# InkTime_Schematic.net
KiCad netlist of a schematic drawn in EAGLE
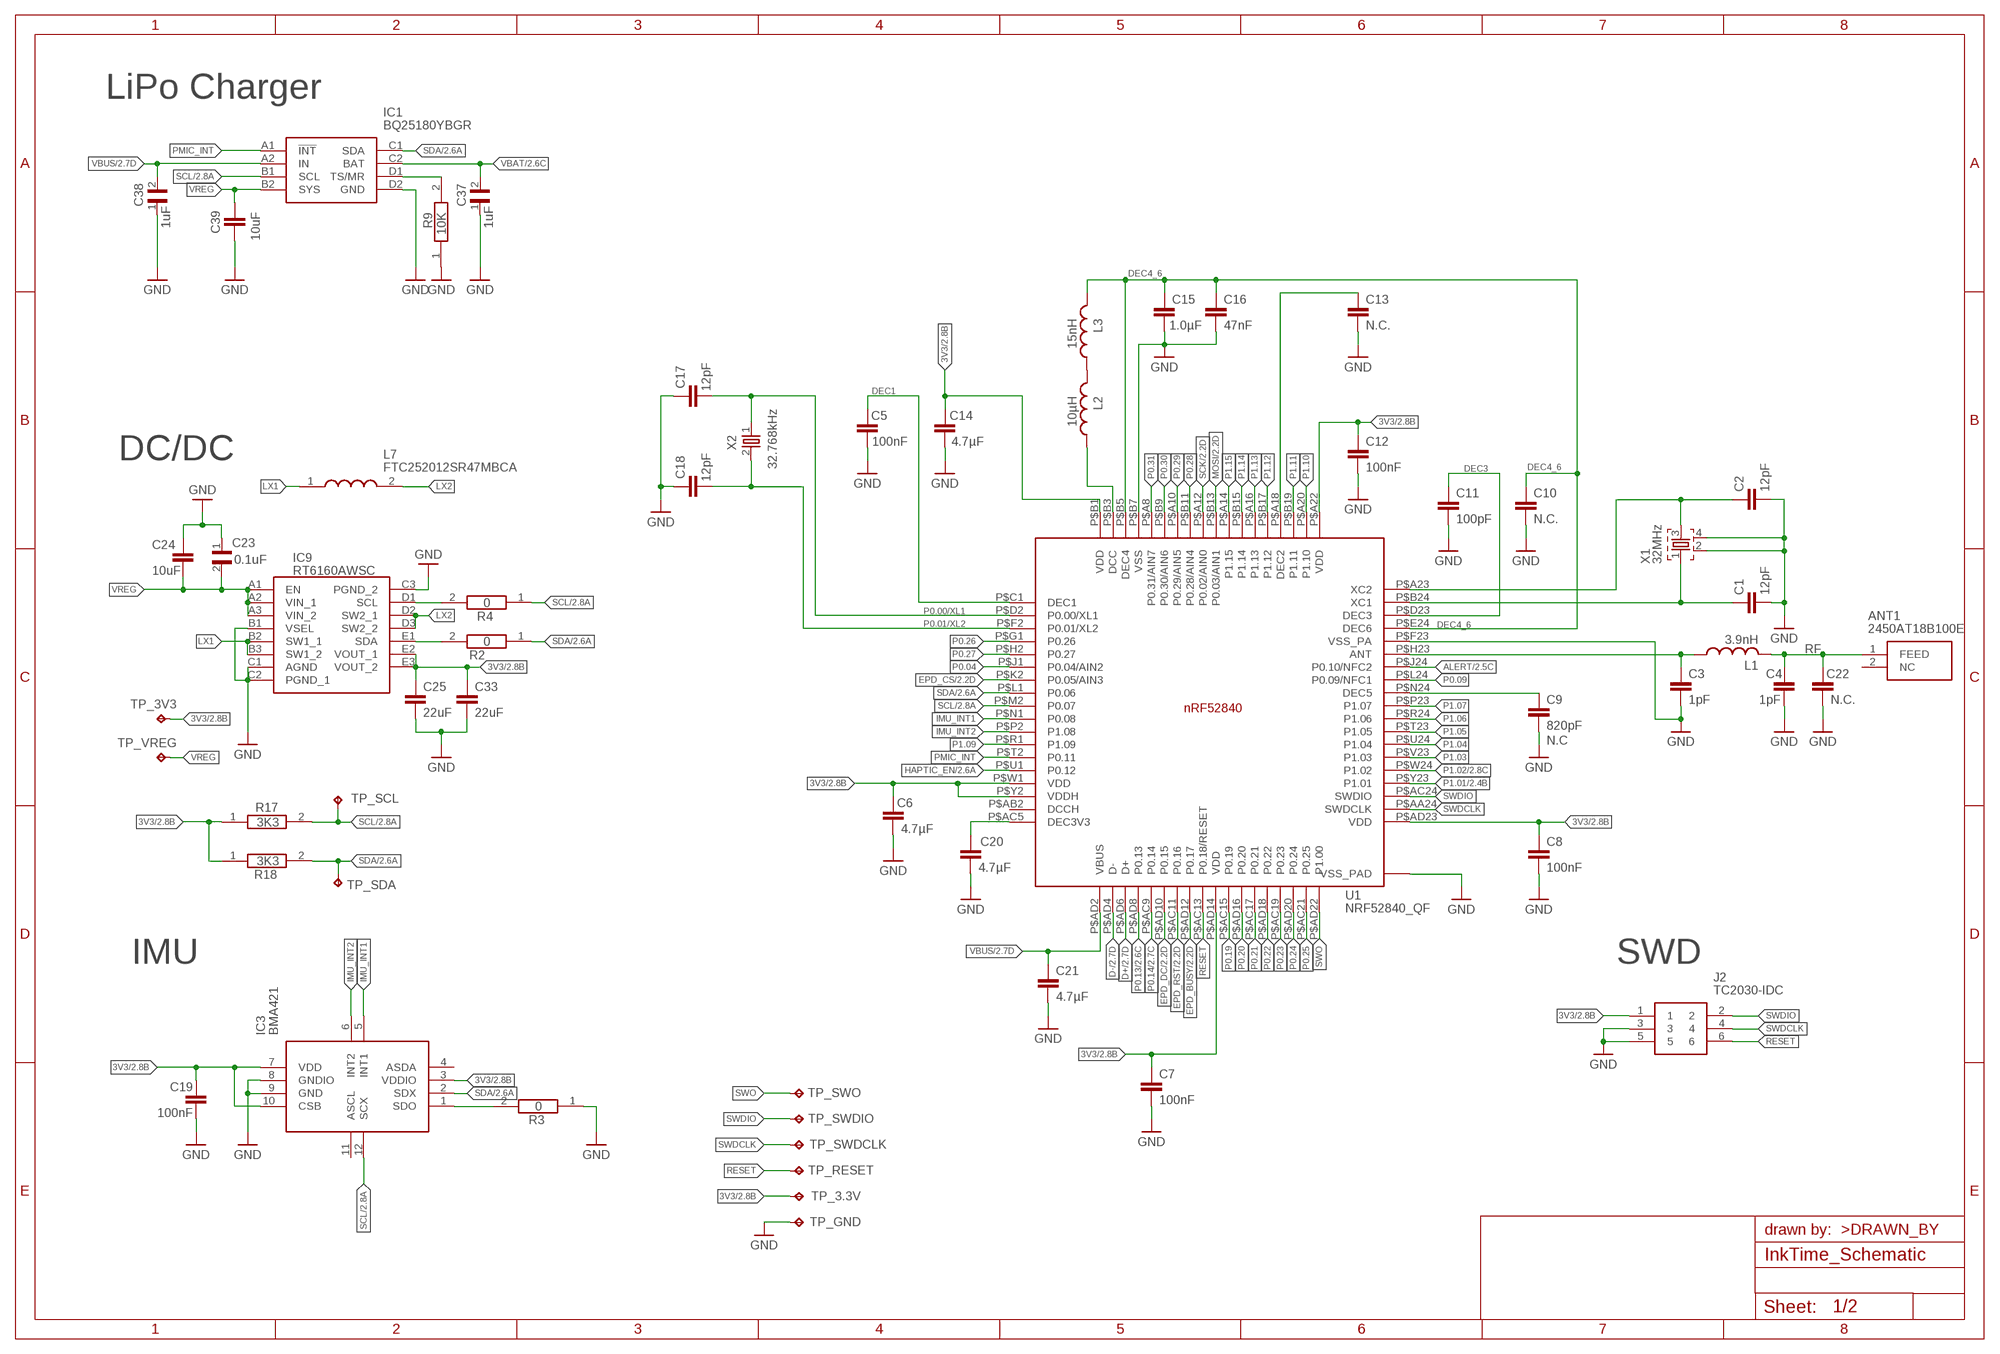
[diagram p0: schematic, sheet 1]
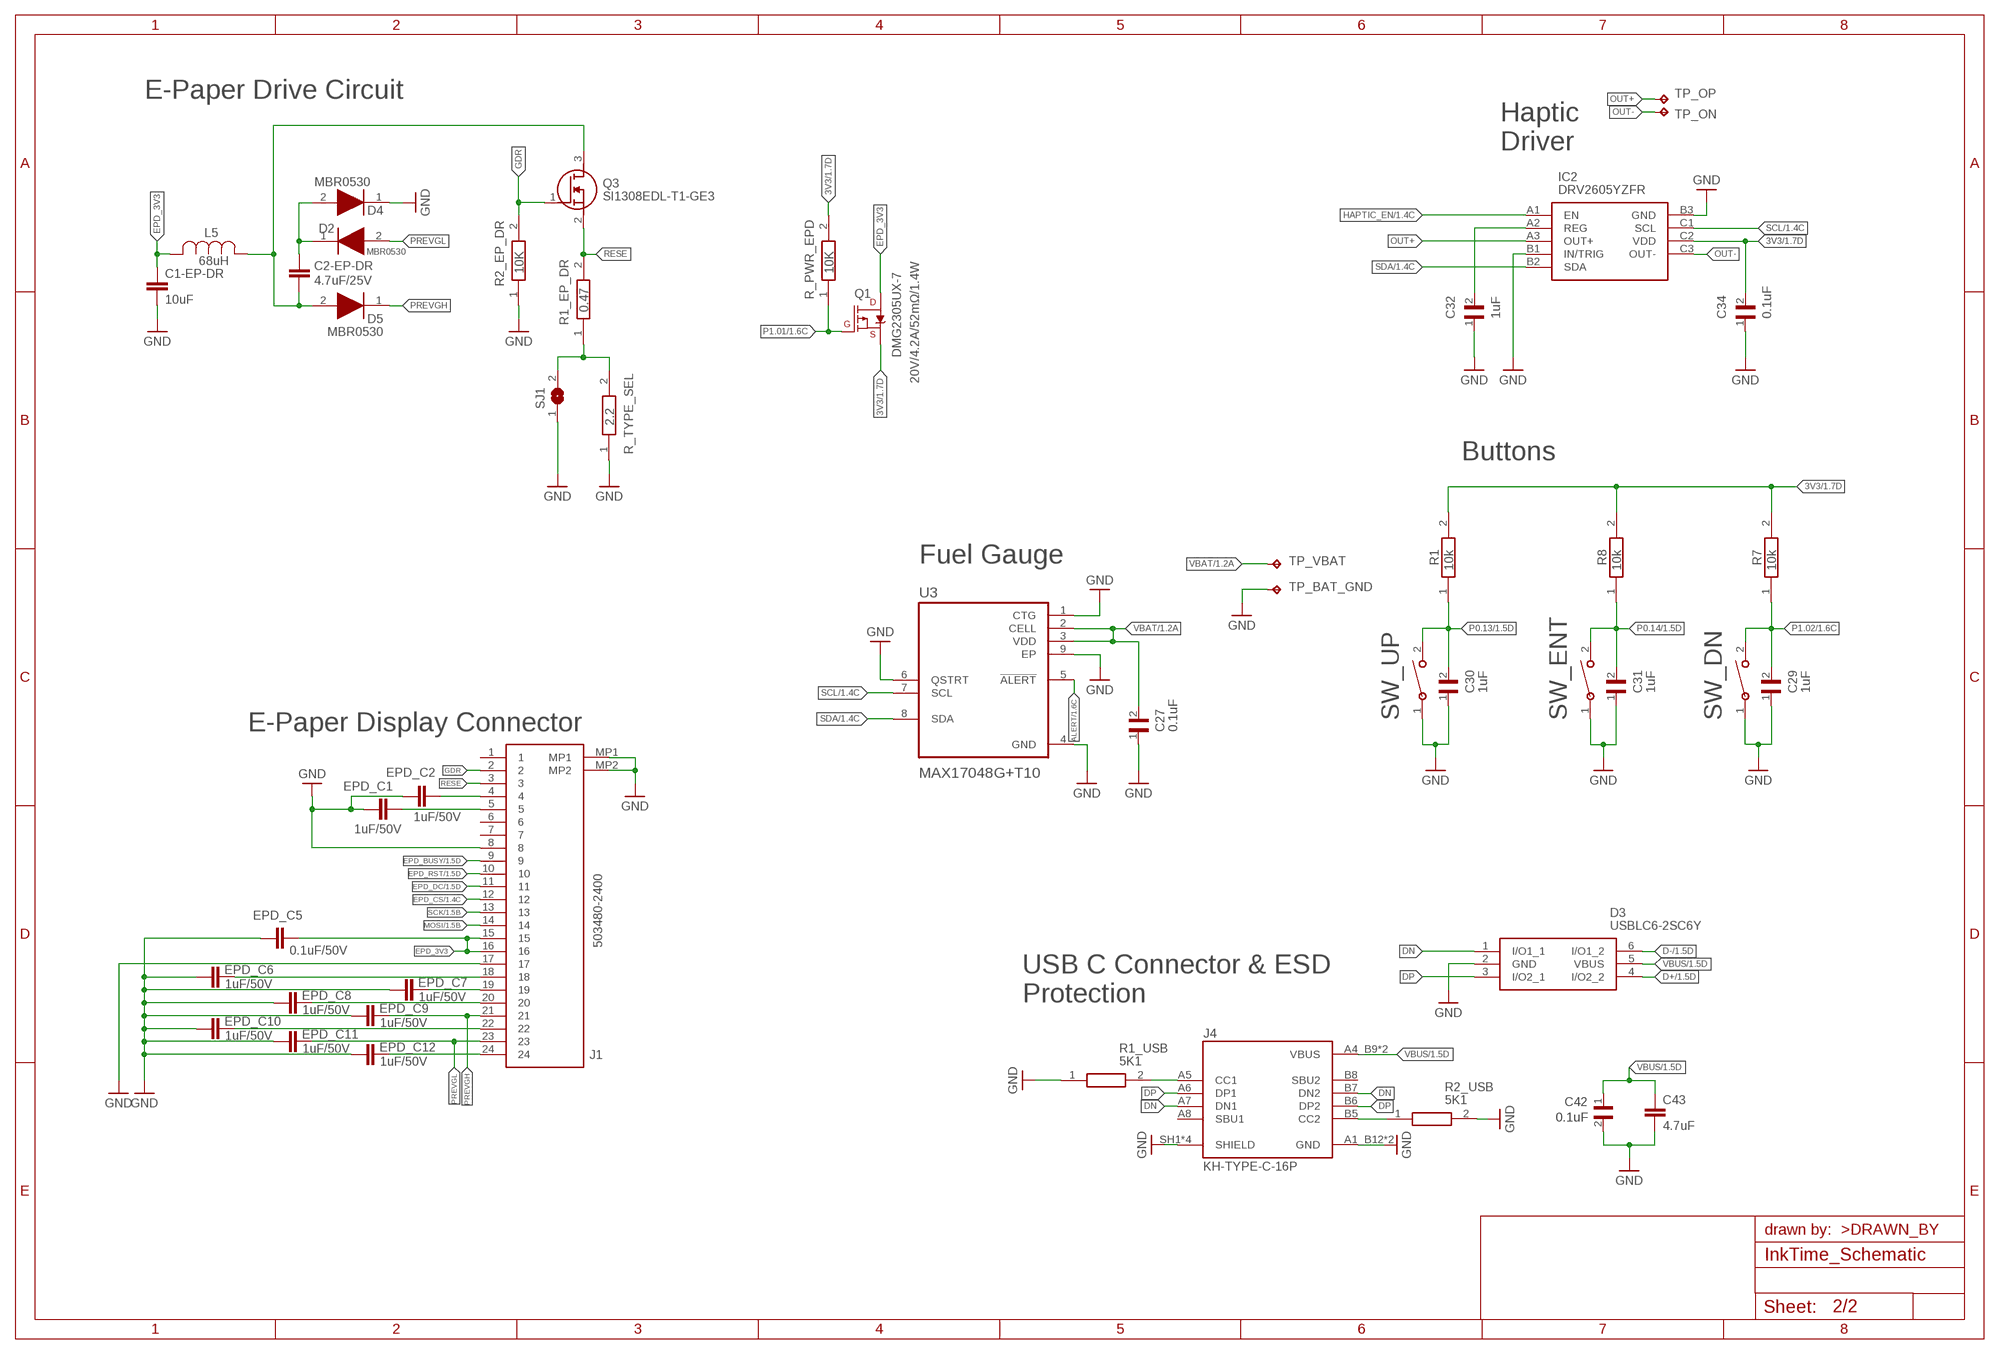
[diagram p1: schematic, sheet 2]

(export (version "E")
  (design (tool "Eeschema 10.0.6"))
  (components
    (comp (ref "C1-EP-DR")
      (value "10uF")
      (footprint "eagle-import:NORDIC_NRF_3_RESC0402_L")
      (libsource (lib "eagle-import") (part "NORDIC_NRF_3_CAPACITOR_0402_L"))
    )
    (comp (ref "C2-EP-DR")
      (value "4.7uF/25V")
      (footprint "eagle-import:NORDIC_NRF_3_RESC0402_L")
      (libsource (lib "eagle-import") (part "NORDIC_NRF_3_CAPACITOR_0402_L"))
    )
    (comp (ref "C27")
      (value "0.1uF")
      (footprint "eagle-import:GRM011R60J152KE01L_1_0201")
      (libsource (lib "eagle-import") (part "GRM011R60J152KE01L_1_GRM011R60J152KE01L"))
    )
    (comp (ref "C29")
      (value "1uF")
      (footprint "eagle-import:GRM011R60J152KE01L_1_0201")
      (libsource (lib "eagle-import") (part "GRM011R60J152KE01L_1_GRM011R60J152KE01L"))
    )
    (comp (ref "C30")
      (value "1uF")
      (footprint "eagle-import:GRM011R60J152KE01L_1_0201")
      (libsource (lib "eagle-import") (part "GRM011R60J152KE01L_1_GRM011R60J152KE01L"))
    )
    (comp (ref "C31")
      (value "1uF")
      (footprint "eagle-import:GRM011R60J152KE01L_1_0201")
      (libsource (lib "eagle-import") (part "GRM011R60J152KE01L_1_GRM011R60J152KE01L"))
    )
    (comp (ref "C32")
      (value "1uF")
      (footprint "eagle-import:GRM011R60J152KE01L_1_0201")
      (libsource (lib "eagle-import") (part "GRM011R60J152KE01L_1_GRM011R60J152KE01L"))
    )
    (comp (ref "C34")
      (value "0.1uF")
      (footprint "eagle-import:GRM011R60J152KE01L_1_0201")
      (libsource (lib "eagle-import") (part "GRM011R60J152KE01L_1_GRM011R60J152KE01L"))
    )
    (comp (ref "C42")
      (value "0.1uF")
      (footprint "eagle-import:GRM011R60J152KE01L_1_0201")
      (libsource (lib "eagle-import") (part "GRM011R60J152KE01L_1_GRM011R60J152KE01L"))
    )
    (comp (ref "C43")
      (value "4.7uF")
      (footprint "eagle-import:NORDIC_NRF_3_RESC0402_L")
      (libsource (lib "eagle-import") (part "NORDIC_NRF_3_CAPACITOR_0402_L"))
    )
    (comp (ref "D2")
      (value "MBR0530")
      (footprint "eagle-import:ESP32_C6_LIBRARY_5_SOD3716X135N")
      (fields (field (name "MF") "ON Semiconductor"))
      (libsource (lib "eagle-import") (part "ESP32_C6_LIBRARY_5_MBR0530"))
    )
    (comp (ref "D3")
      (value "USBLC6-2SC6Y")
      (footprint "eagle-import:ESP32_C6_LIBRARY_3_SOT95P280X145-6N")
      (fields (field (name "MF") "STMicroelectronics"))
      (libsource (lib "eagle-import") (part "ESP32_C6_LIBRARY_3_USBLC6-2SC6Y"))
    )
    (comp (ref "D4")
      (value "MBR0530")
      (footprint "eagle-import:ESP32_C6_LIBRARY_5_SOD3716X135N")
      (fields (field (name "MF") "ON Semiconductor"))
      (libsource (lib "eagle-import") (part "ESP32_C6_LIBRARY_5_MBR0530"))
    )
    (comp (ref "D5")
      (value "MBR0530")
      (footprint "eagle-import:ESP32_C6_LIBRARY_5_SOD3716X135N")
      (fields (field (name "MF") "ON Semiconductor"))
      (libsource (lib "eagle-import") (part "ESP32_C6_LIBRARY_5_MBR0530"))
    )
    (comp (ref "EPD_C1")
      (value "1uF/50V")
      (footprint "eagle-import:NORDIC_NRF_3_RESC0402_L")
      (libsource (lib "eagle-import") (part "NORDIC_NRF_3_CAPACITOR_0402_L"))
    )
    (comp (ref "EPD_C2")
      (value "1uF/50V")
      (footprint "eagle-import:NORDIC_NRF_3_RESC0402_L")
      (libsource (lib "eagle-import") (part "NORDIC_NRF_3_CAPACITOR_0402_L"))
    )
    (comp (ref "EPD_C5")
      (value "0.1uF/50V")
      (footprint "eagle-import:NORDIC_NRF_3_RESC0201_L")
      (libsource (lib "eagle-import") (part "NORDIC_NRF_3_CAPACITOR_0201_L"))
    )
    (comp (ref "EPD_C6")
      (value "1uF/50V")
      (footprint "eagle-import:NORDIC_NRF_3_RESC0402_L")
      (libsource (lib "eagle-import") (part "NORDIC_NRF_3_CAPACITOR_0402_L"))
    )
    (comp (ref "EPD_C7")
      (value "1uF/50V")
      (footprint "eagle-import:NORDIC_NRF_3_RESC0402_L")
      (libsource (lib "eagle-import") (part "NORDIC_NRF_3_CAPACITOR_0402_L"))
    )
    (comp (ref "EPD_C8")
      (value "1uF/50V")
      (footprint "eagle-import:NORDIC_NRF_3_RESC0402_L")
      (libsource (lib "eagle-import") (part "NORDIC_NRF_3_CAPACITOR_0402_L"))
    )
    (comp (ref "EPD_C9")
      (value "1uF/50V")
      (footprint "eagle-import:NORDIC_NRF_3_RESC0402_L")
      (libsource (lib "eagle-import") (part "NORDIC_NRF_3_CAPACITOR_0402_L"))
    )
    (comp (ref "EPD_C10")
      (value "1uF/50V")
      (footprint "eagle-import:NORDIC_NRF_3_RESC0402_L")
      (libsource (lib "eagle-import") (part "NORDIC_NRF_3_CAPACITOR_0402_L"))
    )
    (comp (ref "EPD_C11")
      (value "1uF/50V")
      (footprint "eagle-import:NORDIC_NRF_3_RESC0402_L")
      (libsource (lib "eagle-import") (part "NORDIC_NRF_3_CAPACITOR_0402_L"))
    )
    (comp (ref "EPD_C12")
      (value "1uF/50V")
      (footprint "eagle-import:NORDIC_NRF_3_RESC0402_L")
      (libsource (lib "eagle-import") (part "NORDIC_NRF_3_CAPACITOR_0402_L"))
    )
    (comp (ref "IC2")
      (value "DRV2605YZFR")
      (footprint "eagle-import:DRV2605YZFR_BGA9C50P3X3_144X144X62")
      (libsource (lib "eagle-import") (part "DRV2605YZFR_DRV2605YZFR"))
    )
    (comp (ref "J1")
      (value "503480-2400")
      (footprint "eagle-import:503480-2400_5034802400")
      (fields (field (name "MOUSER_PART_NUMBER") "538-503480-2400"))
      (libsource (lib "eagle-import") (part "503480-2400_503480-2400"))
    )
    (comp (ref "J4")
      (value "KH-TYPE-C-16P")
      (footprint "eagle-import:KH-TYPE-C-16P_KINGHELM_KH-TYPE-C-16P")
      (fields (field (name "MF") "kinghelm"))
      (libsource (lib "eagle-import") (part "KH-TYPE-C-16P_KH-TYPE-C-16P"))
    )
    (comp (ref "L5")
      (value "68uH")
      (footprint "eagle-import:ESP32_C6_LIBRARY_2_IND_4828-WE-TPC_WRE")
      (fields
        (field (name "MANUFACTURER_PART_NUMBER") "744043680")
        (field (name "COPYRIGHT") "Copyright (C) 2024 Ultra Librarian. All rights reserved.")
      )
      (libsource (lib "eagle-import") (part "ESP32_C6_LIBRARY_2_744043680IND_4828-WE-TPC_WRE"))
    )
    (comp (ref "Q1")
      (value "20V/4.2A/52mΩ/1.4W")
      (footprint "eagle-import:ESP32_C6_LIBRARY_4_ESP32_C6_LIBRARY_4_ESP32_C6_LIBRARY_4_ESP32_C6_LIBRARY_4_ESP32_WROVER_SPARKFUN-DISCRETESEMI_SOT23-3")
      (libsource (lib "eagle-import") (part "ESP32_C6_LIBRARY_4_ESP32_WROVER_SPARKFUN-DISCRETESEMI_MOSFET_PCH-DMG2305UX-7"))
    )
    (comp (ref "Q3")
      (value "SI1308EDL-T1-GE3")
      (footprint "eagle-import:ESP32_C6_LIBRARY_6_SOT65P210X110-3N")
      (fields (field (name "MF") "Vishay Siliconix"))
      (libsource (lib "eagle-import") (part "ESP32_C6_LIBRARY_6_SI1308EDL-T1-GE3"))
    )
    (comp (ref "R1")
      (value "10k")
      (footprint "eagle-import:CPF0201D7K68C1_0201")
      (libsource (lib "eagle-import") (part "CPF0201D7K68C1_CPF0201D7K68C1"))
    )
    (comp (ref "R1_EP_DR")
      (value "0.47")
      (footprint "eagle-import:CPF0201D7K68C1_0201")
      (libsource (lib "eagle-import") (part "CPF0201D7K68C1_CPF0201D7K68C1"))
    )
    (comp (ref "R1_USB")
      (value "5K1")
      (footprint "eagle-import:CPF0201D7K68C1_0201")
      (libsource (lib "eagle-import") (part "CPF0201D7K68C1_CPF0201D7K68C1"))
    )
    (comp (ref "R2_EP_DR")
      (value "10K")
      (footprint "eagle-import:CPF0201D7K68C1_0201")
      (libsource (lib "eagle-import") (part "CPF0201D7K68C1_CPF0201D7K68C1"))
    )
    (comp (ref "R2_USB")
      (value "5K1")
      (footprint "eagle-import:CPF0201D7K68C1_0201")
      (libsource (lib "eagle-import") (part "CPF0201D7K68C1_CPF0201D7K68C1"))
    )
    (comp (ref "R7")
      (value "10k")
      (footprint "eagle-import:CPF0201D7K68C1_0201")
      (libsource (lib "eagle-import") (part "CPF0201D7K68C1_CPF0201D7K68C1"))
    )
    (comp (ref "R8")
      (value "10k")
      (footprint "eagle-import:CPF0201D7K68C1_0201")
      (libsource (lib "eagle-import") (part "CPF0201D7K68C1_CPF0201D7K68C1"))
    )
    (comp (ref "R_PWR_EPD")
      (value "10K")
      (footprint "eagle-import:CPF0201D7K68C1_0201")
      (libsource (lib "eagle-import") (part "CPF0201D7K68C1_CPF0201D7K68C1"))
    )
    (comp (ref "R_TYPE_SEL")
      (value "2.2")
      (footprint "eagle-import:CPF0201D7K68C1_0201")
      (libsource (lib "eagle-import") (part "CPF0201D7K68C1_CPF0201D7K68C1"))
    )
    (comp (ref "SJ1")
      (value "ESP32_C6_LIBRARY_7_JUMPER_SJ")
      (footprint "eagle-import:ESP32_C6_LIBRARY_7_JUMPER_SJ")
      (libsource (lib "eagle-import") (part "ESP32_C6_LIBRARY_7_JUMPER_SJ"))
    )
    (comp (ref "SW_DN")
      (value "2025-10-22_07-23-44_LIBRARY_EVP-AKE31ASW_EVP-AKE31A_PAN")
      (footprint "eagle-import:2025-10-22_07-23-44_LIBRARY_SW_EVP-AKE31A_PAN")
      (fields
        (field (name "MANUFACTURER_PART_NUMBER") "EVP-AKE31A")
        (field (name "COPYRIGHT") "Copyright (C) 2025 Ultra Librarian. All rights reserved.")
      )
      (libsource (lib "eagle-import") (part "2025-10-22_07-23-44_LIBRARY_EVP-AKE31ASW_EVP-AKE31A_PAN"))
    )
    (comp (ref "SW_ENT")
      (value "2025-10-22_07-23-44_LIBRARY_EVP-AKE31ASW_EVP-AKE31A_PAN")
      (footprint "eagle-import:2025-10-22_07-23-44_LIBRARY_SW_EVP-AKE31A_PAN")
      (fields
        (field (name "MANUFACTURER_PART_NUMBER") "EVP-AKE31A")
        (field (name "COPYRIGHT") "Copyright (C) 2025 Ultra Librarian. All rights reserved.")
      )
      (libsource (lib "eagle-import") (part "2025-10-22_07-23-44_LIBRARY_EVP-AKE31ASW_EVP-AKE31A_PAN"))
    )
    (comp (ref "SW_UP")
      (value "2025-10-22_07-23-44_LIBRARY_EVP-AKE31ASW_EVP-AKE31A_PAN")
      (footprint "eagle-import:2025-10-22_07-23-44_LIBRARY_SW_EVP-AKE31A_PAN")
      (fields
        (field (name "MANUFACTURER_PART_NUMBER") "EVP-AKE31A")
        (field (name "COPYRIGHT") "Copyright (C) 2025 Ultra Librarian. All rights reserved.")
      )
      (libsource (lib "eagle-import") (part "2025-10-22_07-23-44_LIBRARY_EVP-AKE31ASW_EVP-AKE31A_PAN"))
    )
    (comp (ref "TP_BAT_GND")
      (value "HECTOR_WATCH_1_TPTP20R")
      (footprint "eagle-import:HECTOR_WATCH_1_TP20R")
      (libsource (lib "eagle-import") (part "HECTOR_WATCH_1_TPTP20R"))
    )
    (comp (ref "TP_ON")
      (value "HECTOR_WATCH_1_TPTP20R")
      (footprint "eagle-import:HECTOR_WATCH_1_TP20R")
      (libsource (lib "eagle-import") (part "HECTOR_WATCH_1_TPTP20R"))
    )
    (comp (ref "TP_OP")
      (value "HECTOR_WATCH_1_TPTP20R")
      (footprint "eagle-import:HECTOR_WATCH_1_TP20R")
      (libsource (lib "eagle-import") (part "HECTOR_WATCH_1_TPTP20R"))
    )
    (comp (ref "TP_VBAT")
      (value "HECTOR_WATCH_1_TPTP20R")
      (footprint "eagle-import:HECTOR_WATCH_1_TP20R")
      (libsource (lib "eagle-import") (part "HECTOR_WATCH_1_TPTP20R"))
    )
    (comp (ref "U3")
      (value "MAX17048G+T10")
      (footprint "eagle-import:ESP32_C6_LIBRARY_SON50P200X200X80-9N")
      (fields (field (name "MF") "Analog Devices"))
      (libsource (lib "eagle-import") (part "ESP32_C6_LIBRARY_MAX17048G+T10"))
    )
    (comp (ref "ANT1")
      (value "2450AT18B100E")
      (footprint "eagle-import:2450AT18B100E_ANTC3216X140N")
      (fields (field (name "MOUSER_PART_NUMBER") "609-2450AT18B100E"))
      (libsource (lib "eagle-import") (part "2450AT18B100E_2450AT18B100E"))
    )
    (comp (ref "C1")
      (value "12pF")
      (footprint "eagle-import:NORDIC_NRF_3_RESC0201_L")
      (libsource (lib "eagle-import") (part "NORDIC_NRF_3_CAPACITOR_0201_L"))
    )
    (comp (ref "C2")
      (value "12pF")
      (footprint "eagle-import:NORDIC_NRF_3_RESC0201_L")
      (libsource (lib "eagle-import") (part "NORDIC_NRF_3_CAPACITOR_0201_L"))
    )
    (comp (ref "C3")
      (value "1pF")
      (footprint "eagle-import:NORDIC_NRF_3_RESC0201_L")
      (libsource (lib "eagle-import") (part "NORDIC_NRF_3_CAPACITOR_0201_L"))
    )
    (comp (ref "C4")
      (value "1pF")
      (footprint "eagle-import:NORDIC_NRF_3_RESC0201_L")
      (libsource (lib "eagle-import") (part "NORDIC_NRF_3_CAPACITOR_0201_L"))
    )
    (comp (ref "C5")
      (value "100nF")
      (footprint "eagle-import:NORDIC_NRF_3_RESC0201_L")
      (libsource (lib "eagle-import") (part "NORDIC_NRF_3_CAPACITOR_0201_L"))
    )
    (comp (ref "C6")
      (value "4.7µF")
      (footprint "eagle-import:NORDIC_NRF_3_RESC0402_L")
      (libsource (lib "eagle-import") (part "NORDIC_NRF_3_CAPACITOR_0402_L"))
    )
    (comp (ref "C7")
      (value "100nF")
      (footprint "eagle-import:NORDIC_NRF_3_RESC0201_L")
      (libsource (lib "eagle-import") (part "NORDIC_NRF_3_CAPACITOR_0201_L"))
    )
    (comp (ref "C8")
      (value "100nF")
      (footprint "eagle-import:NORDIC_NRF_3_RESC0201_L")
      (libsource (lib "eagle-import") (part "NORDIC_NRF_3_CAPACITOR_0201_L"))
    )
    (comp (ref "C9")
      (value "820pF")
      (footprint "eagle-import:NORDIC_NRF_3_RESC0201_L")
      (libsource (lib "eagle-import") (part "NORDIC_NRF_3_CAPACITOR_0201_L"))
    )
    (comp (ref "C10")
      (value "N.C.")
      (footprint "eagle-import:NORDIC_NRF_3_RESC0201_L")
      (libsource (lib "eagle-import") (part "NORDIC_NRF_3_CAPACITOR_0201_L"))
    )
    (comp (ref "C11")
      (value "100pF")
      (footprint "eagle-import:NORDIC_NRF_3_RESC0201_L")
      (libsource (lib "eagle-import") (part "NORDIC_NRF_3_CAPACITOR_0201_L"))
    )
    (comp (ref "C12")
      (value "100nF")
      (footprint "eagle-import:NORDIC_NRF_3_RESC0201_L")
      (libsource (lib "eagle-import") (part "NORDIC_NRF_3_CAPACITOR_0201_L"))
    )
    (comp (ref "C13")
      (value "N.C.")
      (footprint "eagle-import:NORDIC_NRF_3_RESC0201_L")
      (libsource (lib "eagle-import") (part "NORDIC_NRF_3_CAPACITOR_0201_L"))
    )
    (comp (ref "C14")
      (value "4.7µF")
      (footprint "eagle-import:NORDIC_NRF_3_RESC0402_L")
      (libsource (lib "eagle-import") (part "NORDIC_NRF_3_CAPACITOR_0402_L"))
    )
    (comp (ref "C15")
      (value "1.0µF")
      (footprint "eagle-import:NORDIC_NRF_3_RESC0402_L")
      (libsource (lib "eagle-import") (part "NORDIC_NRF_3_CAPACITOR_0402_L"))
    )
    (comp (ref "C16")
      (value "47nF")
      (footprint "eagle-import:NORDIC_NRF_3_RESC0201_L")
      (libsource (lib "eagle-import") (part "NORDIC_NRF_3_CAPACITOR_0201_L"))
    )
    (comp (ref "C17")
      (value "12pF")
      (footprint "eagle-import:NORDIC_NRF_3_RESC0201_L")
      (libsource (lib "eagle-import") (part "NORDIC_NRF_3_CAPACITOR_0201_L"))
    )
    (comp (ref "C18")
      (value "12pF")
      (footprint "eagle-import:NORDIC_NRF_3_RESC0201_L")
      (libsource (lib "eagle-import") (part "NORDIC_NRF_3_CAPACITOR_0201_L"))
    )
    (comp (ref "C19")
      (value "100nF")
      (footprint "eagle-import:NORDIC_NRF_3_RESC0201_L")
      (libsource (lib "eagle-import") (part "NORDIC_NRF_3_CAPACITOR_0201_L"))
    )
    (comp (ref "C20")
      (value "4.7µF")
      (footprint "eagle-import:NORDIC_NRF_3_RESC0402_L")
      (libsource (lib "eagle-import") (part "NORDIC_NRF_3_CAPACITOR_0402_L"))
    )
    (comp (ref "C21")
      (value "4.7µF")
      (footprint "eagle-import:NORDIC_NRF_3_RESC0402_L")
      (libsource (lib "eagle-import") (part "NORDIC_NRF_3_CAPACITOR_0402_L"))
    )
    (comp (ref "C22")
      (value "N.C.")
      (footprint "eagle-import:NORDIC_NRF_3_RESC0201_L")
      (libsource (lib "eagle-import") (part "NORDIC_NRF_3_CAPACITOR_0201_L"))
    )
    (comp (ref "C23")
      (value "0.1uF")
      (footprint "eagle-import:GRM011R60J152KE01L_1_0201")
      (libsource (lib "eagle-import") (part "GRM011R60J152KE01L_1_GRM011R60J152KE01L"))
    )
    (comp (ref "C24")
      (value "10uF")
      (footprint "eagle-import:NORDIC_NRF_3_RESC0402_L")
      (libsource (lib "eagle-import") (part "NORDIC_NRF_3_CAPACITOR_0402_L"))
    )
    (comp (ref "C25")
      (value "22uF")
      (footprint "eagle-import:NORDIC_NRF_3_RESC0402_L")
      (libsource (lib "eagle-import") (part "NORDIC_NRF_3_CAPACITOR_0402_L"))
    )
    (comp (ref "C33")
      (value "22uF")
      (footprint "eagle-import:NORDIC_NRF_3_RESC0402_L")
      (libsource (lib "eagle-import") (part "NORDIC_NRF_3_CAPACITOR_0402_L"))
    )
    (comp (ref "C37")
      (value "1uF")
      (footprint "eagle-import:GRM011R60J152KE01L_1_0201")
      (libsource (lib "eagle-import") (part "GRM011R60J152KE01L_1_GRM011R60J152KE01L"))
    )
    (comp (ref "C38")
      (value "1uF")
      (footprint "eagle-import:GRM011R60J152KE01L_1_0201")
      (libsource (lib "eagle-import") (part "GRM011R60J152KE01L_1_GRM011R60J152KE01L"))
    )
    (comp (ref "C39")
      (value "10uF")
      (footprint "eagle-import:NORDIC_NRF_3_RESC0402_L")
      (libsource (lib "eagle-import") (part "NORDIC_NRF_3_CAPACITOR_0402_L"))
    )
    (comp (ref "IC1")
      (value "BQ25180YBGR")
      (footprint "eagle-import:BQ25180YBGR_BGA8C40P2X4_100X155X50")
      (fields (field (name "MOUSER_PART_NUMBER") "595-BQ25180YBGR"))
      (libsource (lib "eagle-import") (part "BQ25180YBGR_BQ25180YBGR"))
    )
    (comp (ref "IC3")
      (value "BMA421")
      (footprint "eagle-import:BMA423_BMA423")
      (fields (field (name "ARROW_PART_NUMBER") "BMA423") (field (name "MOUSER_PART_NUMBER") "262-BMA423"))
      (libsource (lib "eagle-import") (part "BMA423_BMA423"))
    )
    (comp (ref "IC9")
      (value "RT6160AWSC")
      (footprint "eagle-import:RT6160AWSC_BGA15C40P3X5_140X230X60")
      (fields (field (name "MOUSER_PART_NUMBER") "835-RT6160AWSC"))
      (libsource (lib "eagle-import") (part "RT6160AWSC_RT6160AWSC"))
    )
    (comp (ref "J2")
      (value "TC2030-IDC")
      (footprint "eagle-import:TC2030-IDC_TC2030IDC")
      (libsource (lib "eagle-import") (part "TC2030-IDC_TC2030-IDC"))
    )
    (comp (ref "L1")
      (value "3.9nH")
      (footprint "eagle-import:NORDIC_NRF_2_RESC0402_L")
      (libsource (lib "eagle-import") (part "NORDIC_NRF_2_INDUCTOR_0402_L"))
    )
    (comp (ref "L2")
      (value "10µH")
      (footprint "eagle-import:NORDIC_NRF_2_RESC0402_L")
      (libsource (lib "eagle-import") (part "NORDIC_NRF_2_INDUCTOR_0402_L"))
    )
    (comp (ref "L3")
      (value "15nH")
      (footprint "eagle-import:NORDIC_NRF_2_RESC0402_L")
      (libsource (lib "eagle-import") (part "NORDIC_NRF_2_INDUCTOR_0402_L"))
    )
    (comp (ref "L7")
      (value "FTC252012SR47MBCA")
      (footprint "eagle-import:MLP2016SR47MT0S1_INDC2016X100N")
      (libsource (lib "eagle-import") (part "MLP2016SR47MT0S1_FTC252012SR47MBCA"))
    )
    (comp (ref "R2")
      (value "0")
      (footprint "eagle-import:CPF0201D7K68C1_0201")
      (libsource (lib "eagle-import") (part "CPF0201D7K68C1_CPF0201D7K68C1"))
    )
    (comp (ref "R3")
      (value "0")
      (footprint "eagle-import:CPF0201D7K68C1_0201")
      (libsource (lib "eagle-import") (part "CPF0201D7K68C1_CPF0201D7K68C1"))
    )
    (comp (ref "R4")
      (value "0")
      (footprint "eagle-import:CPF0201D7K68C1_0201")
      (libsource (lib "eagle-import") (part "CPF0201D7K68C1_CPF0201D7K68C1"))
    )
    (comp (ref "R9")
      (value "10K")
      (footprint "eagle-import:CPF0201D7K68C1_0201")
      (libsource (lib "eagle-import") (part "CPF0201D7K68C1_CPF0201D7K68C1"))
    )
    (comp (ref "R17")
      (value "3K3")
      (footprint "eagle-import:CPF0201D7K68C1_0201")
      (libsource (lib "eagle-import") (part "CPF0201D7K68C1_CPF0201D7K68C1"))
    )
    (comp (ref "R18")
      (value "3K3")
      (footprint "eagle-import:CPF0201D7K68C1_0201")
      (libsource (lib "eagle-import") (part "CPF0201D7K68C1_CPF0201D7K68C1"))
    )
    (comp (ref "TP_3.3V")
      (value "HECTOR_WATCH_1_TPTP20R")
      (footprint "eagle-import:HECTOR_WATCH_1_TP20R")
      (libsource (lib "eagle-import") (part "HECTOR_WATCH_1_TPTP20R"))
    )
    (comp (ref "TP_3V3")
      (value "HECTOR_WATCH_1_TPTP20R")
      (footprint "eagle-import:HECTOR_WATCH_1_TP20R")
      (libsource (lib "eagle-import") (part "HECTOR_WATCH_1_TPTP20R"))
    )
    (comp (ref "TP_GND")
      (value "HECTOR_WATCH_1_TPTP20R")
      (footprint "eagle-import:HECTOR_WATCH_1_TP20R")
      (libsource (lib "eagle-import") (part "HECTOR_WATCH_1_TPTP20R"))
    )
    (comp (ref "TP_RESET")
      (value "HECTOR_WATCH_1_TPTP20R")
      (footprint "eagle-import:HECTOR_WATCH_1_TP20R")
      (libsource (lib "eagle-import") (part "HECTOR_WATCH_1_TPTP20R"))
    )
    (comp (ref "TP_SCL")
      (value "HECTOR_WATCH_1_TPTP20R")
      (footprint "eagle-import:HECTOR_WATCH_1_TP20R")
      (libsource (lib "eagle-import") (part "HECTOR_WATCH_1_TPTP20R"))
    )
    (comp (ref "TP_SDA")
      (value "HECTOR_WATCH_1_TPTP20R")
      (footprint "eagle-import:HECTOR_WATCH_1_TP20R")
      (libsource (lib "eagle-import") (part "HECTOR_WATCH_1_TPTP20R"))
    )
    (comp (ref "TP_SWDCLK")
      (value "HECTOR_WATCH_1_TPTP20R")
      (footprint "eagle-import:HECTOR_WATCH_1_TP20R")
      (libsource (lib "eagle-import") (part "HECTOR_WATCH_1_TPTP20R"))
    )
    (comp (ref "TP_SWDIO")
      (value "HECTOR_WATCH_1_TPTP20R")
      (footprint "eagle-import:HECTOR_WATCH_1_TP20R")
      (libsource (lib "eagle-import") (part "HECTOR_WATCH_1_TPTP20R"))
    )
    (comp (ref "TP_SWO")
      (value "HECTOR_WATCH_1_TPTP20R")
      (footprint "eagle-import:HECTOR_WATCH_1_TP20R")
      (libsource (lib "eagle-import") (part "HECTOR_WATCH_1_TPTP20R"))
    )
    (comp (ref "TP_VREG")
      (value "HECTOR_WATCH_1_TPTP20R")
      (footprint "eagle-import:HECTOR_WATCH_1_TP20R")
      (libsource (lib "eagle-import") (part "HECTOR_WATCH_1_TPTP20R"))
    )
    (comp (ref "U1")
      (value "NRF52840_QF")
      (footprint "eagle-import:NORDIC_NRF_4_AQFN50P700X700X85_HS-74N")
      (libsource (lib "eagle-import") (part "NORDIC_NRF_4_NRF52840_QF"))
    )
    (comp (ref "X1")
      (value "32MHz")
      (footprint "eagle-import:NORDIC_NRF_BT-XTAL_2016_N")
      (libsource (lib "eagle-import") (part "NORDIC_NRF_XTAL_32MHZ"))
    )
    (comp (ref "X2")
      (value "32.768kHz")
      (footprint "eagle-import:NORDIC_NRF_1_XTAL_3215_N")
      (libsource (lib "eagle-import") (part "NORDIC_NRF_1_XTAL_32KHZ"))
    )
  )
  (nets
    (net (code "1") (name "3V3") (class "Default")
      (node (ref "C12") (pin "1") (pinfunction "1_1") (pintype "passive"))
      (node (ref "C14") (pin "2") (pinfunction "2_2") (pintype "passive"))
      (node (ref "C19") (pin "1") (pinfunction "1_1") (pintype "passive"))
      (node (ref "C25") (pin "1") (pinfunction "1_1") (pintype "passive"))
      (node (ref "C33") (pin "1") (pinfunction "1_1") (pintype "passive"))
      (node (ref "C34") (pin "2") (pinfunction "2_2") (pintype "passive"))
      (node (ref "C6") (pin "2") (pinfunction "2_2") (pintype "passive"))
      (node (ref "C7") (pin "1") (pinfunction "1_1") (pintype "passive"))
      (node (ref "C8") (pin "1") (pinfunction "1_1") (pintype "passive"))
      (node (ref "IC2") (pin "C2") (pinfunction "VDD_C2") (pintype "bidirectional"))
      (node (ref "IC3") (pin "10") (pinfunction "CSB_10") (pintype "bidirectional"))
      (node (ref "IC3") (pin "3") (pinfunction "VDDIO_3") (pintype "bidirectional"))
      (node (ref "IC3") (pin "7") (pinfunction "VDD_7") (pintype "bidirectional"))
      (node (ref "IC9") (pin "E2") (pinfunction "VOUT_1_E2") (pintype "bidirectional"))
      (node (ref "IC9") (pin "E3") (pinfunction "VOUT_2_E3") (pintype "bidirectional"))
      (node (ref "J2") (pin "1") (pinfunction "1_1") (pintype "bidirectional"))
      (node (ref "Q1") (pin "2") (pinfunction "S_2") (pintype "bidirectional"))
      (node (ref "R1") (pin "2") (pinfunction "2_2") (pintype "bidirectional"))
      (node (ref "R17") (pin "1") (pinfunction "1_1") (pintype "bidirectional"))
      (node (ref "R18") (pin "1") (pinfunction "1_1") (pintype "bidirectional"))
      (node (ref "R7") (pin "2") (pinfunction "2_2") (pintype "bidirectional"))
      (node (ref "R8") (pin "2") (pinfunction "2_2") (pintype "bidirectional"))
      (node (ref "R_PWR_EPD") (pin "2") (pinfunction "2_2") (pintype "bidirectional"))
      (node (ref "TP_3.3V") (pin "TP") (pinfunction "TP_TP") (pintype "input"))
      (node (ref "TP_3V3") (pin "TP") (pinfunction "TP_TP") (pintype "input"))
      (node (ref "U1") (pin "P$A22") (pinfunction "VDD_P$A22") (pintype "power_in"))
      (node (ref "U1") (pin "P$AD14") (pinfunction "VDD_P$AD14") (pintype "power_in"))
      (node (ref "U1") (pin "P$AD23") (pinfunction "VDD_P$AD23") (pintype "power_in"))
      (node (ref "U1") (pin "P$B1") (pinfunction "VDD_P$B1") (pintype "power_in"))
      (node (ref "U1") (pin "P$W1") (pinfunction "VDD_P$W1") (pintype "power_in"))
      (node (ref "U1") (pin "P$Y2") (pinfunction "VDDH_P$Y2") (pintype "power_in"))
    )
    (net (code "2") (name "ALERT") (class "Default")
      (node (ref "U1") (pin "P$J24") (pinfunction "P0.10/NFC2_P$J24") (pintype "bidirectional"))
      (node (ref "U3") (pin "5") (pinfunction "~{ALERT}_5") (pintype "output"))
    )
    (net (code "3") (name "D+") (class "Default")
      (node (ref "D3") (pin "4") (pinfunction "I/O2_2_4") (pintype "bidirectional"))
      (node (ref "U1") (pin "P$AD6") (pinfunction "D+_P$AD6") (pintype "bidirectional"))
    )
    (net (code "4") (name "D-") (class "Default")
      (node (ref "D3") (pin "6") (pinfunction "I/O1_2_6") (pintype "bidirectional"))
      (node (ref "U1") (pin "P$AD4") (pinfunction "D-_P$AD4") (pintype "bidirectional"))
    )
    (net (code "5") (name "DN") (class "Default")
      (node (ref "D3") (pin "1") (pinfunction "I/O1_1_1") (pintype "bidirectional"))
      (node (ref "J4") (pin "A7") (pinfunction "DN1_A7") (pintype "bidirectional"))
      (node (ref "J4") (pin "B7") (pinfunction "DN2_B7") (pintype "bidirectional"))
    )
    (net (code "6") (name "DP") (class "Default")
      (node (ref "D3") (pin "3") (pinfunction "I/O2_1_3") (pintype "bidirectional"))
      (node (ref "J4") (pin "A6") (pinfunction "DP1_A6") (pintype "bidirectional"))
      (node (ref "J4") (pin "B6") (pinfunction "DP2_B6") (pintype "bidirectional"))
    )
    (net (code "7") (name "EPD_3V3") (class "Default")
      (node (ref "C1-EP-DR") (pin "1") (pinfunction "1_1") (pintype "passive"))
      (node (ref "EPD_C5") (pin "2") (pinfunction "2_2") (pintype "passive"))
      (node (ref "J1") (pin "15") (pinfunction "15_15") (pintype "bidirectional"))
      (node (ref "J1") (pin "16") (pinfunction "16_16") (pintype "bidirectional"))
      (node (ref "L5") (pin "2") (pinfunction "2_2") (pintype "passive"))
      (node (ref "Q1") (pin "3") (pinfunction "D_3") (pintype "bidirectional"))
    )
    (net (code "8") (name "EPD_BUSY") (class "Default")
      (node (ref "J1") (pin "9") (pinfunction "9_9") (pintype "bidirectional"))
      (node (ref "U1") (pin "P$AD12") (pinfunction "P0.17_P$AD12") (pintype "bidirectional"))
    )
    (net (code "9") (name "EPD_CS") (class "Default")
      (node (ref "J1") (pin "12") (pinfunction "12_12") (pintype "bidirectional"))
      (node (ref "U1") (pin "P$K2") (pinfunction "P0.05/AIN3_P$K2") (pintype "bidirectional"))
    )
    (net (code "10") (name "EPD_DC") (class "Default")
      (node (ref "J1") (pin "11") (pinfunction "11_11") (pintype "bidirectional"))
      (node (ref "U1") (pin "P$AD10") (pinfunction "P0.15_P$AD10") (pintype "bidirectional"))
    )
    (net (code "11") (name "EPD_RST") (class "Default")
      (node (ref "J1") (pin "10") (pinfunction "10_10") (pintype "bidirectional"))
      (node (ref "U1") (pin "P$AC11") (pinfunction "P0.16_P$AC11") (pintype "bidirectional"))
    )
    (net (code "12") (name "GDR") (class "Default")
      (node (ref "J1") (pin "2") (pinfunction "2_2") (pintype "bidirectional"))
      (node (ref "Q3") (pin "1") (pinfunction "G_1") (pintype "bidirectional"))
      (node (ref "R2_EP_DR") (pin "2") (pinfunction "2_2") (pintype "bidirectional"))
    )
    (net (code "13") (name "GND") (class "Default")
      (node (ref "C1") (pin "2") (pinfunction "2_2") (pintype "passive"))
      (node (ref "C1-EP-DR") (pin "2") (pinfunction "2_2") (pintype "passive"))
      (node (ref "C10") (pin "2") (pinfunction "2_2") (pintype "passive"))
      (node (ref "C11") (pin "2") (pinfunction "2_2") (pintype "passive"))
      (node (ref "C12") (pin "2") (pinfunction "2_2") (pintype "passive"))
      (node (ref "C13") (pin "2") (pinfunction "2_2") (pintype "passive"))
      (node (ref "C14") (pin "1") (pinfunction "1_1") (pintype "passive"))
      (node (ref "C15") (pin "2") (pinfunction "2_2") (pintype "passive"))
      (node (ref "C16") (pin "2") (pinfunction "2_2") (pintype "passive"))
      (node (ref "C17") (pin "1") (pinfunction "1_1") (pintype "passive"))
      (node (ref "C18") (pin "1") (pinfunction "1_1") (pintype "passive"))
      (node (ref "C19") (pin "2") (pinfunction "2_2") (pintype "passive"))
      (node (ref "C2") (pin "2") (pinfunction "2_2") (pintype "passive"))
      (node (ref "C20") (pin "1") (pinfunction "1_1") (pintype "passive"))
      (node (ref "C21") (pin "2") (pinfunction "2_2") (pintype "passive"))
      (node (ref "C22") (pin "2") (pinfunction "2_2") (pintype "passive"))
      (node (ref "C23") (pin "1") (pinfunction "1_1") (pintype "passive"))
      (node (ref "C24") (pin "1") (pinfunction "1_1") (pintype "passive"))
      (node (ref "C25") (pin "2") (pinfunction "2_2") (pintype "passive"))
      (node (ref "C27") (pin "1") (pinfunction "1_1") (pintype "passive"))
      (node (ref "C29") (pin "1") (pinfunction "1_1") (pintype "passive"))
      (node (ref "C3") (pin "2") (pinfunction "2_2") (pintype "passive"))
      (node (ref "C30") (pin "1") (pinfunction "1_1") (pintype "passive"))
      (node (ref "C31") (pin "1") (pinfunction "1_1") (pintype "passive"))
      (node (ref "C32") (pin "1") (pinfunction "1_1") (pintype "passive"))
      (node (ref "C33") (pin "2") (pinfunction "2_2") (pintype "passive"))
      (node (ref "C34") (pin "1") (pinfunction "1_1") (pintype "passive"))
      (node (ref "C37") (pin "1") (pinfunction "1_1") (pintype "passive"))
      (node (ref "C38") (pin "1") (pinfunction "1_1") (pintype "passive"))
      (node (ref "C39") (pin "2") (pinfunction "2_2") (pintype "passive"))
      (node (ref "C4") (pin "2") (pinfunction "2_2") (pintype "passive"))
      (node (ref "C42") (pin "2") (pinfunction "2_2") (pintype "passive"))
      (node (ref "C43") (pin "2") (pinfunction "2_2") (pintype "passive"))
      (node (ref "C5") (pin "1") (pinfunction "1_1") (pintype "passive"))
      (node (ref "C6") (pin "1") (pinfunction "1_1") (pintype "passive"))
      (node (ref "C7") (pin "2") (pinfunction "2_2") (pintype "passive"))
      (node (ref "C8") (pin "2") (pinfunction "2_2") (pintype "passive"))
      (node (ref "C9") (pin "2") (pinfunction "2_2") (pintype "passive"))
      (node (ref "D3") (pin "2") (pinfunction "GND_2") (pintype "bidirectional"))
      (node (ref "D4") (pin "1") (pinfunction "K_1") (pintype "bidirectional"))
      (node (ref "EPD_C1") (pin "1") (pinfunction "1_1") (pintype "passive"))
      (node (ref "EPD_C10") (pin "1") (pinfunction "1_1") (pintype "passive"))
      (node (ref "EPD_C11") (pin "1") (pinfunction "1_1") (pintype "passive"))
      (node (ref "EPD_C12") (pin "1") (pinfunction "1_1") (pintype "passive"))
      (node (ref "EPD_C2") (pin "1") (pinfunction "1_1") (pintype "passive"))
      (node (ref "EPD_C5") (pin "1") (pinfunction "1_1") (pintype "passive"))
      (node (ref "EPD_C6") (pin "1") (pinfunction "1_1") (pintype "passive"))
      (node (ref "EPD_C7") (pin "1") (pinfunction "1_1") (pintype "passive"))
      (node (ref "EPD_C8") (pin "1") (pinfunction "1_1") (pintype "passive"))
      (node (ref "EPD_C9") (pin "1") (pinfunction "1_1") (pintype "passive"))
      (node (ref "IC1") (pin "D2") (pinfunction "GND_D2") (pintype "bidirectional"))
      (node (ref "IC2") (pin "B1") (pinfunction "IN/TRIG_B1") (pintype "bidirectional"))
      (node (ref "IC2") (pin "B3") (pinfunction "GND_B3") (pintype "bidirectional"))
      (node (ref "IC3") (pin "8") (pinfunction "GNDIO_8") (pintype "bidirectional"))
      (node (ref "IC3") (pin "9") (pinfunction "GND_9") (pintype "bidirectional"))
      (node (ref "IC9") (pin "B1") (pinfunction "VSEL_B1") (pintype "bidirectional"))
      (node (ref "IC9") (pin "C1") (pinfunction "AGND_C1") (pintype "bidirectional"))
      (node (ref "IC9") (pin "C2") (pinfunction "PGND_1_C2") (pintype "bidirectional"))
      (node (ref "IC9") (pin "C3") (pinfunction "PGND_2_C3") (pintype "bidirectional"))
      (node (ref "J1") (pin "17") (pinfunction "17_17") (pintype "bidirectional"))
      (node (ref "J1") (pin "8") (pinfunction "8_8") (pintype "bidirectional"))
      (node (ref "J1") (pin "MP1") (pinfunction "MP1_MP1") (pintype "bidirectional"))
      (node (ref "J1") (pin "MP2") (pinfunction "MP2_MP2") (pintype "bidirectional"))
      (node (ref "J2") (pin "3") (pinfunction "3_3") (pintype "bidirectional"))
      (node (ref "J2") (pin "5") (pinfunction "5_5") (pintype "bidirectional"))
      (node (ref "J4") (pin "A12_B1") (pinfunction "GND_A12_B1") (pintype "power_in"))
      (node (ref "J4") (pin "A1_B12") (pinfunction "GND_A1_B12") (pintype "power_in"))
      (node (ref "J4") (pin "SH1") (pinfunction "SHIELD_SH1") (pintype "passive"))
      (node (ref "J4") (pin "SH2") (pinfunction "SHIELD_SH2") (pintype "passive"))
      (node (ref "J4") (pin "SH3") (pinfunction "SHIELD_SH3") (pintype "passive"))
      (node (ref "J4") (pin "SH4") (pinfunction "SHIELD_SH4") (pintype "passive"))
      (node (ref "R1_USB") (pin "1") (pinfunction "1_1") (pintype "bidirectional"))
      (node (ref "R2_EP_DR") (pin "1") (pinfunction "1_1") (pintype "bidirectional"))
      (node (ref "R2_USB") (pin "2") (pinfunction "2_2") (pintype "bidirectional"))
      (node (ref "R3") (pin "1") (pinfunction "1_1") (pintype "bidirectional"))
      (node (ref "R9") (pin "1") (pinfunction "1_1") (pintype "bidirectional"))
      (node (ref "R_TYPE_SEL") (pin "1") (pinfunction "1_1") (pintype "bidirectional"))
      (node (ref "SJ1") (pin "1") (pinfunction "1_1") (pintype "passive"))
      (node (ref "SW_DN") (pin "1") (pinfunction "1_1") (pintype "passive"))
      (node (ref "SW_ENT") (pin "1") (pinfunction "1_1") (pintype "passive"))
      (node (ref "SW_UP") (pin "1") (pinfunction "1_1") (pintype "passive"))
      (node (ref "TP_BAT_GND") (pin "TP") (pinfunction "TP_TP") (pintype "input"))
      (node (ref "TP_GND") (pin "TP") (pinfunction "TP_TP") (pintype "input"))
      (node (ref "U1") (pin "P$74") (pinfunction "VSS_PAD_P$74") (pintype "bidirectional"))
      (node (ref "U1") (pin "P$75") (pinfunction "VSS_PAD_P$75") (pintype "bidirectional"))
      (node (ref "U1") (pin "P$76") (pinfunction "VSS_PAD_P$76") (pintype "bidirectional"))
      (node (ref "U1") (pin "P$77") (pinfunction "VSS_PAD_P$77") (pintype "bidirectional"))
      (node (ref "U1") (pin "P$78") (pinfunction "VSS_PAD_P$78") (pintype "bidirectional"))
      (node (ref "U1") (pin "P$79") (pinfunction "VSS_PAD_P$79") (pintype "bidirectional"))
      (node (ref "U1") (pin "P$80") (pinfunction "VSS_PAD_P$80") (pintype "bidirectional"))
      (node (ref "U1") (pin "P$81") (pinfunction "VSS_PAD_P$81") (pintype "bidirectional"))
      (node (ref "U1") (pin "P$82") (pinfunction "VSS_PAD_P$82") (pintype "bidirectional"))
      (node (ref "U1") (pin "P$83") (pinfunction "VSS_PAD_P$83") (pintype "bidirectional"))
      (node (ref "U1") (pin "P$84") (pinfunction "VSS_PAD_P$84") (pintype "bidirectional"))
      (node (ref "U1") (pin "P$85") (pinfunction "VSS_PAD_P$85") (pintype "bidirectional"))
      (node (ref "U1") (pin "P$86") (pinfunction "VSS_PAD_P$86") (pintype "bidirectional"))
      (node (ref "U1") (pin "P$87") (pinfunction "VSS_PAD_P$87") (pintype "bidirectional"))
      (node (ref "U1") (pin "P$88") (pinfunction "VSS_PAD_P$88") (pintype "bidirectional"))
      (node (ref "U1") (pin "P$89") (pinfunction "VSS_PAD_P$89") (pintype "bidirectional"))
      (node (ref "U1") (pin "P$90") (pinfunction "VSS_PAD_P$90") (pintype "bidirectional"))
      (node (ref "U1") (pin "P$B7") (pinfunction "VSS_P$B7") (pintype "power_in"))
      (node (ref "U1") (pin "P$F23") (pinfunction "VSS_PA_P$F23") (pintype "bidirectional"))
      (node (ref "U3") (pin "1") (pinfunction "CTG_1") (pintype "power_in"))
      (node (ref "U3") (pin "4") (pinfunction "GND_4") (pintype "power_in"))
      (node (ref "U3") (pin "6") (pinfunction "QSTRT_6") (pintype "input"))
      (node (ref "U3") (pin "9") (pinfunction "EP_9") (pintype "power_in"))
      (node (ref "X1") (pin "2") (pinfunction "2_2") (pintype "passive"))
      (node (ref "X1") (pin "4") (pinfunction "4_4") (pintype "passive"))
    )
    (net (code "14") (name "HAPTIC_EN") (class "Default")
      (node (ref "IC2") (pin "A1") (pinfunction "EN_A1") (pintype "bidirectional"))
      (node (ref "U1") (pin "P$U1") (pinfunction "P0.12_P$U1") (pintype "bidirectional"))
    )
    (net (code "15") (name "IMU_INT1") (class "Default")
      (node (ref "IC3") (pin "5") (pinfunction "INT1_5") (pintype "bidirectional"))
      (node (ref "U1") (pin "P$N1") (pinfunction "P0.08_P$N1") (pintype "bidirectional"))
    )
    (net (code "16") (name "IMU_INT2") (class "Default")
      (node (ref "IC3") (pin "6") (pinfunction "INT2_6") (pintype "bidirectional"))
      (node (ref "U1") (pin "P$P2") (pinfunction "P1.08_P$P2") (pintype "bidirectional"))
    )
    (net (code "17") (name "LX1") (class "Default")
      (node (ref "IC9") (pin "B2") (pinfunction "SW1_1_B2") (pintype "bidirectional"))
      (node (ref "IC9") (pin "B3") (pinfunction "SW1_2_B3") (pintype "bidirectional"))
      (node (ref "L7") (pin "1") (pinfunction "1_1") (pintype "bidirectional"))
    )
    (net (code "18") (name "LX2") (class "Default")
      (node (ref "IC9") (pin "D2") (pinfunction "SW2_1_D2") (pintype "bidirectional"))
      (node (ref "IC9") (pin "D3") (pinfunction "SW2_2_D3") (pintype "bidirectional"))
      (node (ref "L7") (pin "2") (pinfunction "2_2") (pintype "bidirectional"))
    )
    (net (code "19") (name "MOSI") (class "Default")
      (node (ref "J1") (pin "14") (pinfunction "14_14") (pintype "bidirectional"))
      (node (ref "U1") (pin "P$B13") (pinfunction "P0.03/AIN1_P$B13") (pintype "bidirectional"))
    )
    (net (code "20") (name "Net-(ANT1-FEED)") (class "Default")
      (node (ref "ANT1") (pin "1") (pinfunction "FEED_1") (pintype "input"))
      (node (ref "C22") (pin "1") (pinfunction "1_1") (pintype "passive"))
      (node (ref "C4") (pin "1") (pinfunction "1_1") (pintype "passive"))
      (node (ref "L1") (pin "2") (pinfunction "2_2") (pintype "passive"))
    )
    (net (code "21") (name "Net-(D2-K)") (class "Default")
      (node (ref "C2-EP-DR") (pin "1") (pinfunction "1_1") (pintype "passive"))
      (node (ref "D2") (pin "1") (pinfunction "K_1") (pintype "bidirectional"))
      (node (ref "D4") (pin "2") (pinfunction "A_2") (pintype "bidirectional"))
    )
    (net (code "22") (name "Net-(D5-A)") (class "Default")
      (node (ref "C2-EP-DR") (pin "2") (pinfunction "2_2") (pintype "passive"))
      (node (ref "D5") (pin "2") (pinfunction "A_2") (pintype "bidirectional"))
      (node (ref "L5") (pin "1") (pinfunction "1_1") (pintype "passive"))
      (node (ref "Q3") (pin "3") (pinfunction "D_3") (pintype "bidirectional"))
    )
    (net (code "23") (name "Net-(EPD_C1-Pad2)") (class "Default")
      (node (ref "EPD_C1") (pin "2") (pinfunction "2_2") (pintype "passive"))
      (node (ref "J1") (pin "5") (pinfunction "5_5") (pintype "bidirectional"))
    )
    (net (code "24") (name "Net-(EPD_C2-Pad2)") (class "Default")
      (node (ref "EPD_C2") (pin "2") (pinfunction "2_2") (pintype "passive"))
      (node (ref "J1") (pin "4") (pinfunction "4_4") (pintype "bidirectional"))
    )
    (net (code "25") (name "Net-(EPD_C6-Pad2)") (class "Default")
      (node (ref "EPD_C6") (pin "2") (pinfunction "2_2") (pintype "passive"))
      (node (ref "J1") (pin "18") (pinfunction "18_18") (pintype "bidirectional"))
    )
    (net (code "26") (name "Net-(EPD_C7-Pad2)") (class "Default")
      (node (ref "EPD_C7") (pin "2") (pinfunction "2_2") (pintype "passive"))
      (node (ref "J1") (pin "19") (pinfunction "19_19") (pintype "bidirectional"))
    )
    (net (code "27") (name "Net-(EPD_C8-Pad2)") (class "Default")
      (node (ref "EPD_C8") (pin "2") (pinfunction "2_2") (pintype "passive"))
      (node (ref "J1") (pin "20") (pinfunction "20_20") (pintype "bidirectional"))
    )
    (net (code "28") (name "Net-(EPD_C10-Pad2)") (class "Default")
      (node (ref "EPD_C10") (pin "2") (pinfunction "2_2") (pintype "passive"))
      (node (ref "J1") (pin "22") (pinfunction "22_22") (pintype "bidirectional"))
    )
    (net (code "29") (name "Net-(EPD_C12-Pad2)") (class "Default")
      (node (ref "EPD_C12") (pin "2") (pinfunction "2_2") (pintype "passive"))
      (node (ref "J1") (pin "24") (pinfunction "24_24") (pintype "bidirectional"))
    )
    (net (code "30") (name "Net-(IC1-TS{slash}MR)") (class "Default")
      (node (ref "IC1") (pin "D1") (pinfunction "TS/MR_D1") (pintype "bidirectional"))
      (node (ref "R9") (pin "2") (pinfunction "2_2") (pintype "bidirectional"))
    )
    (net (code "31") (name "Net-(IC2-REG)") (class "Default")
      (node (ref "C32") (pin "2") (pinfunction "2_2") (pintype "passive"))
      (node (ref "IC2") (pin "A2") (pinfunction "REG_A2") (pintype "bidirectional"))
    )
    (net (code "32") (name "Net-(IC3-SDO)") (class "Default")
      (node (ref "IC3") (pin "1") (pinfunction "SDO_1") (pintype "bidirectional"))
      (node (ref "R3") (pin "2") (pinfunction "2_2") (pintype "bidirectional"))
    )
    (net (code "33") (name "Net-(IC9-SCL)") (class "Default")
      (node (ref "IC9") (pin "D1") (pinfunction "SCL_D1") (pintype "bidirectional"))
      (node (ref "R4") (pin "2") (pinfunction "2_2") (pintype "bidirectional"))
    )
    (net (code "34") (name "Net-(IC9-SDA)") (class "Default")
      (node (ref "IC9") (pin "E1") (pinfunction "SDA_E1") (pintype "bidirectional"))
      (node (ref "R2") (pin "2") (pinfunction "2_2") (pintype "bidirectional"))
    )
    (net (code "35") (name "Net-(J4-CC1)") (class "Default")
      (node (ref "J4") (pin "A5") (pinfunction "CC1_A5") (pintype "bidirectional"))
      (node (ref "R1_USB") (pin "2") (pinfunction "2_2") (pintype "bidirectional"))
    )
    (net (code "36") (name "Net-(J4-CC2)") (class "Default")
      (node (ref "J4") (pin "B5") (pinfunction "CC2_B5") (pintype "bidirectional"))
      (node (ref "R2_USB") (pin "1") (pinfunction "1_1") (pintype "bidirectional"))
    )
    (net (code "37") (name "Net-(L2-Pad2)") (class "Default")
      (node (ref "L2") (pin "2") (pinfunction "2_2") (pintype "passive"))
      (node (ref "L3") (pin "1") (pinfunction "1_1") (pintype "passive"))
    )
    (net (code "38") (name "Net-(R1_EP_DR-Pad1)") (class "Default")
      (node (ref "R1_EP_DR") (pin "1") (pinfunction "1_1") (pintype "bidirectional"))
      (node (ref "R_TYPE_SEL") (pin "2") (pinfunction "2_2") (pintype "bidirectional"))
      (node (ref "SJ1") (pin "2") (pinfunction "2_2") (pintype "passive"))
    )
    (net (code "39") (name "Net-(U1-ANT)") (class "Default")
      (node (ref "C3") (pin "1") (pinfunction "1_1") (pintype "passive"))
      (node (ref "L1") (pin "1") (pinfunction "1_1") (pintype "passive"))
      (node (ref "U1") (pin "P$H23") (pinfunction "ANT_P$H23") (pintype "bidirectional"))
    )
    (net (code "40") (name "Net-(U1-DCC)") (class "Default")
      (node (ref "L2") (pin "1") (pinfunction "1_1") (pintype "passive"))
      (node (ref "U1") (pin "P$B3") (pinfunction "DCC_P$B3") (pintype "output"))
    )
    (net (code "41") (name "Net-(U1-DEC1)") (class "Default")
      (node (ref "C5") (pin "2") (pinfunction "2_2") (pintype "passive"))
      (node (ref "U1") (pin "P$C1") (pinfunction "DEC1_P$C1") (pintype "power_in"))
    )
    (net (code "42") (name "Net-(U1-DEC2)") (class "Default")
      (node (ref "C13") (pin "1") (pinfunction "1_1") (pintype "passive"))
      (node (ref "U1") (pin "P$A18") (pinfunction "DEC2_P$A18") (pintype "bidirectional"))
    )
    (net (code "43") (name "Net-(U1-DEC3)") (class "Default")
      (node (ref "C11") (pin "1") (pinfunction "1_1") (pintype "passive"))
      (node (ref "U1") (pin "P$D23") (pinfunction "DEC3_P$D23") (pintype "bidirectional"))
    )
    (net (code "44") (name "Net-(U1-DEC3V3)") (class "Default")
      (node (ref "C20") (pin "2") (pinfunction "2_2") (pintype "passive"))
      (node (ref "U1") (pin "P$AC5") (pinfunction "DEC3V3_P$AC5") (pintype "bidirectional"))
    )
    (net (code "45") (name "Net-(U1-DEC4)") (class "Default")
      (node (ref "C10") (pin "1") (pinfunction "1_1") (pintype "passive"))
      (node (ref "C15") (pin "1") (pinfunction "1_1") (pintype "passive"))
      (node (ref "C16") (pin "1") (pinfunction "1_1") (pintype "passive"))
      (node (ref "L3") (pin "2") (pinfunction "2_2") (pintype "passive"))
      (node (ref "U1") (pin "P$B5") (pinfunction "DEC4_P$B5") (pintype "power_in"))
      (node (ref "U1") (pin "P$E24") (pinfunction "DEC6_P$E24") (pintype "bidirectional"))
    )
    (net (code "46") (name "Net-(U1-DEC5)") (class "Default")
      (node (ref "C9") (pin "1") (pinfunction "1_1") (pintype "passive"))
      (node (ref "U1") (pin "P$N24") (pinfunction "DEC5_P$N24") (pintype "bidirectional"))
    )
    (net (code "47") (name "Net-(U1-P0.00{slash}XL1)") (class "Default")
      (node (ref "C17") (pin "2") (pinfunction "2_2") (pintype "passive"))
      (node (ref "U1") (pin "P$D2") (pinfunction "P0.00/XL1_P$D2") (pintype "bidirectional"))
      (node (ref "X2") (pin "1") (pinfunction "1_1") (pintype "passive"))
    )
    (net (code "48") (name "Net-(U1-P0.01{slash}XL2)") (class "Default")
      (node (ref "C18") (pin "2") (pinfunction "2_2") (pintype "passive"))
      (node (ref "U1") (pin "P$F2") (pinfunction "P0.01/XL2_P$F2") (pintype "bidirectional"))
      (node (ref "X2") (pin "2") (pinfunction "2_2") (pintype "passive"))
    )
    (net (code "49") (name "Net-(U1-XC1)") (class "Default")
      (node (ref "C1") (pin "1") (pinfunction "1_1") (pintype "passive"))
      (node (ref "U1") (pin "P$B24") (pinfunction "XC1_P$B24") (pintype "input"))
      (node (ref "X1") (pin "1") (pinfunction "1_1") (pintype "passive"))
    )
    (net (code "50") (name "Net-(U1-XC2)") (class "Default")
      (node (ref "C2") (pin "1") (pinfunction "1_1") (pintype "passive"))
      (node (ref "U1") (pin "P$A23") (pinfunction "XC2_P$A23") (pintype "output"))
      (node (ref "X1") (pin "3") (pinfunction "3_3") (pintype "passive"))
    )
    (net (code "51") (name "OUT+") (class "Default")
      (node (ref "IC2") (pin "A3") (pinfunction "OUT+_A3") (pintype "bidirectional"))
      (node (ref "TP_OP") (pin "TP") (pinfunction "TP_TP") (pintype "input"))
    )
    (net (code "52") (name "OUT-") (class "Default")
      (node (ref "IC2") (pin "C3") (pinfunction "OUT-_C3") (pintype "bidirectional"))
      (node (ref "TP_ON") (pin "TP") (pinfunction "TP_TP") (pintype "input"))
    )
    (net (code "53") (name "P0.04") (class "Default")
      (node (ref "U1") (pin "P$J1") (pinfunction "P0.04/AIN2_P$J1") (pintype "bidirectional"))
    )
    (net (code "54") (name "P0.09") (class "Default")
      (node (ref "U1") (pin "P$L24") (pinfunction "P0.09/NFC1_P$L24") (pintype "bidirectional"))
    )
    (net (code "55") (name "P0.13") (class "Default")
      (node (ref "C30") (pin "2") (pinfunction "2_2") (pintype "passive"))
      (node (ref "R1") (pin "1") (pinfunction "1_1") (pintype "bidirectional"))
      (node (ref "SW_UP") (pin "2") (pinfunction "2_2") (pintype "passive"))
      (node (ref "U1") (pin "P$AD8") (pinfunction "P0.13_P$AD8") (pintype "bidirectional"))
    )
    (net (code "56") (name "P0.14") (class "Default")
      (node (ref "C31") (pin "2") (pinfunction "2_2") (pintype "passive"))
      (node (ref "R8") (pin "1") (pinfunction "1_1") (pintype "bidirectional"))
      (node (ref "SW_ENT") (pin "2") (pinfunction "2_2") (pintype "passive"))
      (node (ref "U1") (pin "P$AC9") (pinfunction "P0.14_P$AC9") (pintype "bidirectional"))
    )
    (net (code "57") (name "P0.19") (class "Default")
      (node (ref "U1") (pin "P$AD16") (pinfunction "P0.20_P$AD16") (pintype "bidirectional"))
    )
    (net (code "58") (name "P0.20") (class "Default")
      (node (ref "U1") (pin "P$AC15") (pinfunction "P0.19_P$AC15") (pintype "bidirectional"))
    )
    (net (code "59") (name "P0.21") (class "Default")
      (node (ref "U1") (pin "P$AC17") (pinfunction "P0.21_P$AC17") (pintype "bidirectional"))
    )
    (net (code "60") (name "P0.22") (class "Default")
      (node (ref "U1") (pin "P$AD18") (pinfunction "P0.22_P$AD18") (pintype "bidirectional"))
    )
    (net (code "61") (name "P0.23") (class "Default")
      (node (ref "U1") (pin "P$AC19") (pinfunction "P0.23_P$AC19") (pintype "bidirectional"))
    )
    (net (code "62") (name "P0.24") (class "Default")
      (node (ref "U1") (pin "P$AD20") (pinfunction "P0.24_P$AD20") (pintype "bidirectional"))
    )
    (net (code "63") (name "P0.25") (class "Default")
      (node (ref "U1") (pin "P$AC21") (pinfunction "P0.25_P$AC21") (pintype "bidirectional"))
    )
    (net (code "64") (name "P0.26") (class "Default")
      (node (ref "U1") (pin "P$G1") (pinfunction "P0.26_P$G1") (pintype "bidirectional"))
    )
    (net (code "65") (name "P0.27") (class "Default")
      (node (ref "U1") (pin "P$H2") (pinfunction "P0.27_P$H2") (pintype "bidirectional"))
    )
    (net (code "66") (name "P0.28") (class "Default")
      (node (ref "U1") (pin "P$B11") (pinfunction "P0.28/AIN4_P$B11") (pintype "bidirectional"))
    )
    (net (code "67") (name "P0.29") (class "Default")
      (node (ref "U1") (pin "P$A10") (pinfunction "P0.29/AIN5_P$A10") (pintype "bidirectional"))
    )
    (net (code "68") (name "P0.30") (class "Default")
      (node (ref "U1") (pin "P$B9") (pinfunction "P0.30/AIN6_P$B9") (pintype "bidirectional"))
    )
    (net (code "69") (name "P0.31") (class "Default")
      (node (ref "U1") (pin "P$A8") (pinfunction "P0.31/AIN7_P$A8") (pintype "bidirectional"))
    )
    (net (code "70") (name "P1.01") (class "Default")
      (node (ref "Q1") (pin "1") (pinfunction "G_1") (pintype "bidirectional"))
      (node (ref "R_PWR_EPD") (pin "1") (pinfunction "1_1") (pintype "bidirectional"))
      (node (ref "U1") (pin "P$Y23") (pinfunction "P1.01_P$Y23") (pintype "bidirectional"))
    )
    (net (code "71") (name "P1.02") (class "Default")
      (node (ref "C29") (pin "2") (pinfunction "2_2") (pintype "passive"))
      (node (ref "R7") (pin "1") (pinfunction "1_1") (pintype "bidirectional"))
      (node (ref "SW_DN") (pin "2") (pinfunction "2_2") (pintype "passive"))
      (node (ref "U1") (pin "P$W24") (pinfunction "P1.02_P$W24") (pintype "bidirectional"))
    )
    (net (code "72") (name "P1.03") (class "Default")
      (node (ref "U1") (pin "P$V23") (pinfunction "P1.03_P$V23") (pintype "bidirectional"))
    )
    (net (code "73") (name "P1.04") (class "Default")
      (node (ref "U1") (pin "P$U24") (pinfunction "P1.04_P$U24") (pintype "bidirectional"))
    )
    (net (code "74") (name "P1.05") (class "Default")
      (node (ref "U1") (pin "P$T23") (pinfunction "P1.05_P$T23") (pintype "bidirectional"))
    )
    (net (code "75") (name "P1.06") (class "Default")
      (node (ref "U1") (pin "P$R24") (pinfunction "P1.06_P$R24") (pintype "bidirectional"))
    )
    (net (code "76") (name "P1.07") (class "Default")
      (node (ref "U1") (pin "P$P23") (pinfunction "P1.07_P$P23") (pintype "bidirectional"))
    )
    (net (code "77") (name "P1.09") (class "Default")
      (node (ref "U1") (pin "P$R1") (pinfunction "P1.09_P$R1") (pintype "bidirectional"))
    )
    (net (code "78") (name "P1.10") (class "Default")
      (node (ref "U1") (pin "P$A20") (pinfunction "P1.10_P$A20") (pintype "bidirectional"))
    )
    (net (code "79") (name "P1.11") (class "Default")
      (node (ref "U1") (pin "P$B19") (pinfunction "P1.11_P$B19") (pintype "bidirectional"))
    )
    (net (code "80") (name "P1.12") (class "Default")
      (node (ref "U1") (pin "P$B17") (pinfunction "P1.12_P$B17") (pintype "bidirectional"))
    )
    (net (code "81") (name "P1.13") (class "Default")
      (node (ref "U1") (pin "P$A16") (pinfunction "P1.13_P$A16") (pintype "bidirectional"))
    )
    (net (code "82") (name "P1.14") (class "Default")
      (node (ref "U1") (pin "P$B15") (pinfunction "P1.14_P$B15") (pintype "bidirectional"))
    )
    (net (code "83") (name "P1.15") (class "Default")
      (node (ref "U1") (pin "P$A14") (pinfunction "P1.15_P$A14") (pintype "bidirectional"))
    )
    (net (code "84") (name "PMIC_INT") (class "Default")
      (node (ref "IC1") (pin "A1") (pinfunction "~{INT}_A1") (pintype "bidirectional"))
      (node (ref "U1") (pin "P$T2") (pinfunction "P0.11_P$T2") (pintype "bidirectional"))
    )
    (net (code "85") (name "PREVGH") (class "Default")
      (node (ref "D5") (pin "1") (pinfunction "K_1") (pintype "bidirectional"))
      (node (ref "EPD_C9") (pin "2") (pinfunction "2_2") (pintype "passive"))
      (node (ref "J1") (pin "21") (pinfunction "21_21") (pintype "bidirectional"))
    )
    (net (code "86") (name "PREVGL") (class "Default")
      (node (ref "D2") (pin "2") (pinfunction "A_2") (pintype "bidirectional"))
      (node (ref "EPD_C11") (pin "2") (pinfunction "2_2") (pintype "passive"))
      (node (ref "J1") (pin "23") (pinfunction "23_23") (pintype "bidirectional"))
    )
    (net (code "87") (name "RESE") (class "Default")
      (node (ref "J1") (pin "3") (pinfunction "3_3") (pintype "bidirectional"))
      (node (ref "Q3") (pin "2") (pinfunction "S_2") (pintype "bidirectional"))
      (node (ref "R1_EP_DR") (pin "2") (pinfunction "2_2") (pintype "bidirectional"))
    )
    (net (code "88") (name "RESET") (class "Default")
      (node (ref "J2") (pin "6") (pinfunction "6_6") (pintype "bidirectional"))
      (node (ref "TP_RESET") (pin "TP") (pinfunction "TP_TP") (pintype "input"))
      (node (ref "U1") (pin "P$AC13") (pinfunction "P0.18/RESET_P$AC13") (pintype "bidirectional"))
    )
    (net (code "89") (name "SCK") (class "Default")
      (node (ref "J1") (pin "13") (pinfunction "13_13") (pintype "bidirectional"))
      (node (ref "U1") (pin "P$A12") (pinfunction "P0.02/AIN0_P$A12") (pintype "bidirectional"))
    )
    (net (code "90") (name "SCL") (class "Default")
      (node (ref "IC1") (pin "B1") (pinfunction "SCL_B1") (pintype "bidirectional"))
      (node (ref "IC2") (pin "C1") (pinfunction "SCL_C1") (pintype "bidirectional"))
      (node (ref "IC3") (pin "12") (pinfunction "SCX_12") (pintype "bidirectional"))
      (node (ref "R17") (pin "2") (pinfunction "2_2") (pintype "bidirectional"))
      (node (ref "R4") (pin "1") (pinfunction "1_1") (pintype "bidirectional"))
      (node (ref "TP_SCL") (pin "TP") (pinfunction "TP_TP") (pintype "input"))
      (node (ref "U1") (pin "P$M2") (pinfunction "P0.07_P$M2") (pintype "bidirectional"))
      (node (ref "U3") (pin "7") (pinfunction "SCL_7") (pintype "input"))
    )
    (net (code "91") (name "SDA") (class "Default")
      (node (ref "IC1") (pin "C1") (pinfunction "SDA_C1") (pintype "bidirectional"))
      (node (ref "IC2") (pin "B2") (pinfunction "SDA_B2") (pintype "bidirectional"))
      (node (ref "IC3") (pin "2") (pinfunction "SDX_2") (pintype "bidirectional"))
      (node (ref "R18") (pin "2") (pinfunction "2_2") (pintype "bidirectional"))
      (node (ref "R2") (pin "1") (pinfunction "1_1") (pintype "bidirectional"))
      (node (ref "TP_SDA") (pin "TP") (pinfunction "TP_TP") (pintype "input"))
      (node (ref "U1") (pin "P$L1") (pinfunction "P0.06_P$L1") (pintype "bidirectional"))
      (node (ref "U3") (pin "8") (pinfunction "SDA_8") (pintype "bidirectional"))
    )
    (net (code "92") (name "SWDCLK") (class "Default")
      (node (ref "J2") (pin "4") (pinfunction "4_4") (pintype "bidirectional"))
      (node (ref "TP_SWDCLK") (pin "TP") (pinfunction "TP_TP") (pintype "input"))
      (node (ref "U1") (pin "P$AA24") (pinfunction "SWDCLK_P$AA24") (pintype "input"))
    )
    (net (code "93") (name "SWDIO") (class "Default")
      (node (ref "J2") (pin "2") (pinfunction "2_2") (pintype "bidirectional"))
      (node (ref "TP_SWDIO") (pin "TP") (pinfunction "TP_TP") (pintype "input"))
      (node (ref "U1") (pin "P$AC24") (pinfunction "SWDIO_P$AC24") (pintype "bidirectional"))
    )
    (net (code "94") (name "SWO") (class "Default")
      (node (ref "TP_SWO") (pin "TP") (pinfunction "TP_TP") (pintype "input"))
      (node (ref "U1") (pin "P$AD22") (pinfunction "P1.00_P$AD22") (pintype "bidirectional"))
    )
    (net (code "95") (name "VBAT") (class "Default")
      (node (ref "C27") (pin "2") (pinfunction "2_2") (pintype "passive"))
      (node (ref "C37") (pin "2") (pinfunction "2_2") (pintype "passive"))
      (node (ref "IC1") (pin "C2") (pinfunction "BAT_C2") (pintype "bidirectional"))
      (node (ref "TP_VBAT") (pin "TP") (pinfunction "TP_TP") (pintype "input"))
      (node (ref "U3") (pin "2") (pinfunction "CELL_2") (pintype "power_in"))
      (node (ref "U3") (pin "3") (pinfunction "VDD_3") (pintype "power_in"))
    )
    (net (code "96") (name "VBUS") (class "Default")
      (node (ref "C21") (pin "1") (pinfunction "1_1") (pintype "passive"))
      (node (ref "C38") (pin "2") (pinfunction "2_2") (pintype "passive"))
      (node (ref "C42") (pin "1") (pinfunction "1_1") (pintype "passive"))
      (node (ref "C43") (pin "1") (pinfunction "1_1") (pintype "passive"))
      (node (ref "D3") (pin "5") (pinfunction "VBUS_5") (pintype "bidirectional"))
      (node (ref "IC1") (pin "A2") (pinfunction "IN_A2") (pintype "bidirectional"))
      (node (ref "J4") (pin "A4_B9") (pinfunction "VBUS_A4_B9") (pintype "power_in"))
      (node (ref "J4") (pin "A9_B4") (pinfunction "VBUS_A9_B4") (pintype "power_in"))
      (node (ref "U1") (pin "P$AD2") (pinfunction "VBUS_P$AD2") (pintype "power_in"))
    )
    (net (code "97") (name "VREG") (class "Default")
      (node (ref "C23") (pin "2") (pinfunction "2_2") (pintype "passive"))
      (node (ref "C24") (pin "2") (pinfunction "2_2") (pintype "passive"))
      (node (ref "C39") (pin "1") (pinfunction "1_1") (pintype "passive"))
      (node (ref "IC1") (pin "B2") (pinfunction "SYS_B2") (pintype "bidirectional"))
      (node (ref "IC9") (pin "A1") (pinfunction "EN_A1") (pintype "bidirectional"))
      (node (ref "IC9") (pin "A2") (pinfunction "VIN_1_A2") (pintype "bidirectional"))
      (node (ref "IC9") (pin "A3") (pinfunction "VIN_2_A3") (pintype "bidirectional"))
      (node (ref "TP_VREG") (pin "TP") (pinfunction "TP_TP") (pintype "input"))
    )
    (net (code "98") (name "unconnected-(ANT1-NC-Pad2)") (class "Default")
      (node (ref "ANT1") (pin "2") (pinfunction "NC_2") (pintype "no_connect"))
    )
    (net (code "99") (name "unconnected-(IC3-ASCL-Pad11)") (class "Default")
      (node (ref "IC3") (pin "11") (pinfunction "ASCL_11") (pintype "bidirectional"))
    )
    (net (code "100") (name "unconnected-(IC3-ASDA-Pad4)") (class "Default")
      (node (ref "IC3") (pin "4") (pinfunction "ASDA_4") (pintype "bidirectional"))
    )
    (net (code "101") (name "unconnected-(J1-Pad1)") (class "Default")
      (node (ref "J1") (pin "1") (pinfunction "1_1") (pintype "bidirectional"))
    )
    (net (code "102") (name "unconnected-(J1-Pad6)") (class "Default")
      (node (ref "J1") (pin "6") (pinfunction "6_6") (pintype "bidirectional"))
    )
    (net (code "103") (name "unconnected-(J1-Pad7)") (class "Default")
      (node (ref "J1") (pin "7") (pinfunction "7_7") (pintype "bidirectional"))
    )
    (net (code "104") (name "unconnected-(J4-SBU1-PadA8)") (class "Default")
      (node (ref "J4") (pin "A8") (pinfunction "SBU1_A8") (pintype "bidirectional"))
    )
    (net (code "105") (name "unconnected-(J4-SBU2-PadB8)") (class "Default")
      (node (ref "J4") (pin "B8") (pinfunction "SBU2_B8") (pintype "bidirectional"))
    )
    (net (code "106") (name "unconnected-(U1-DCCH-PadP$AB2)") (class "Default")
      (node (ref "U1") (pin "P$AB2") (pinfunction "DCCH_P$AB2") (pintype "bidirectional"))
    )
  )
)
